# IOR8.net
KiCad netlist of a schematic drawn in EAGLE
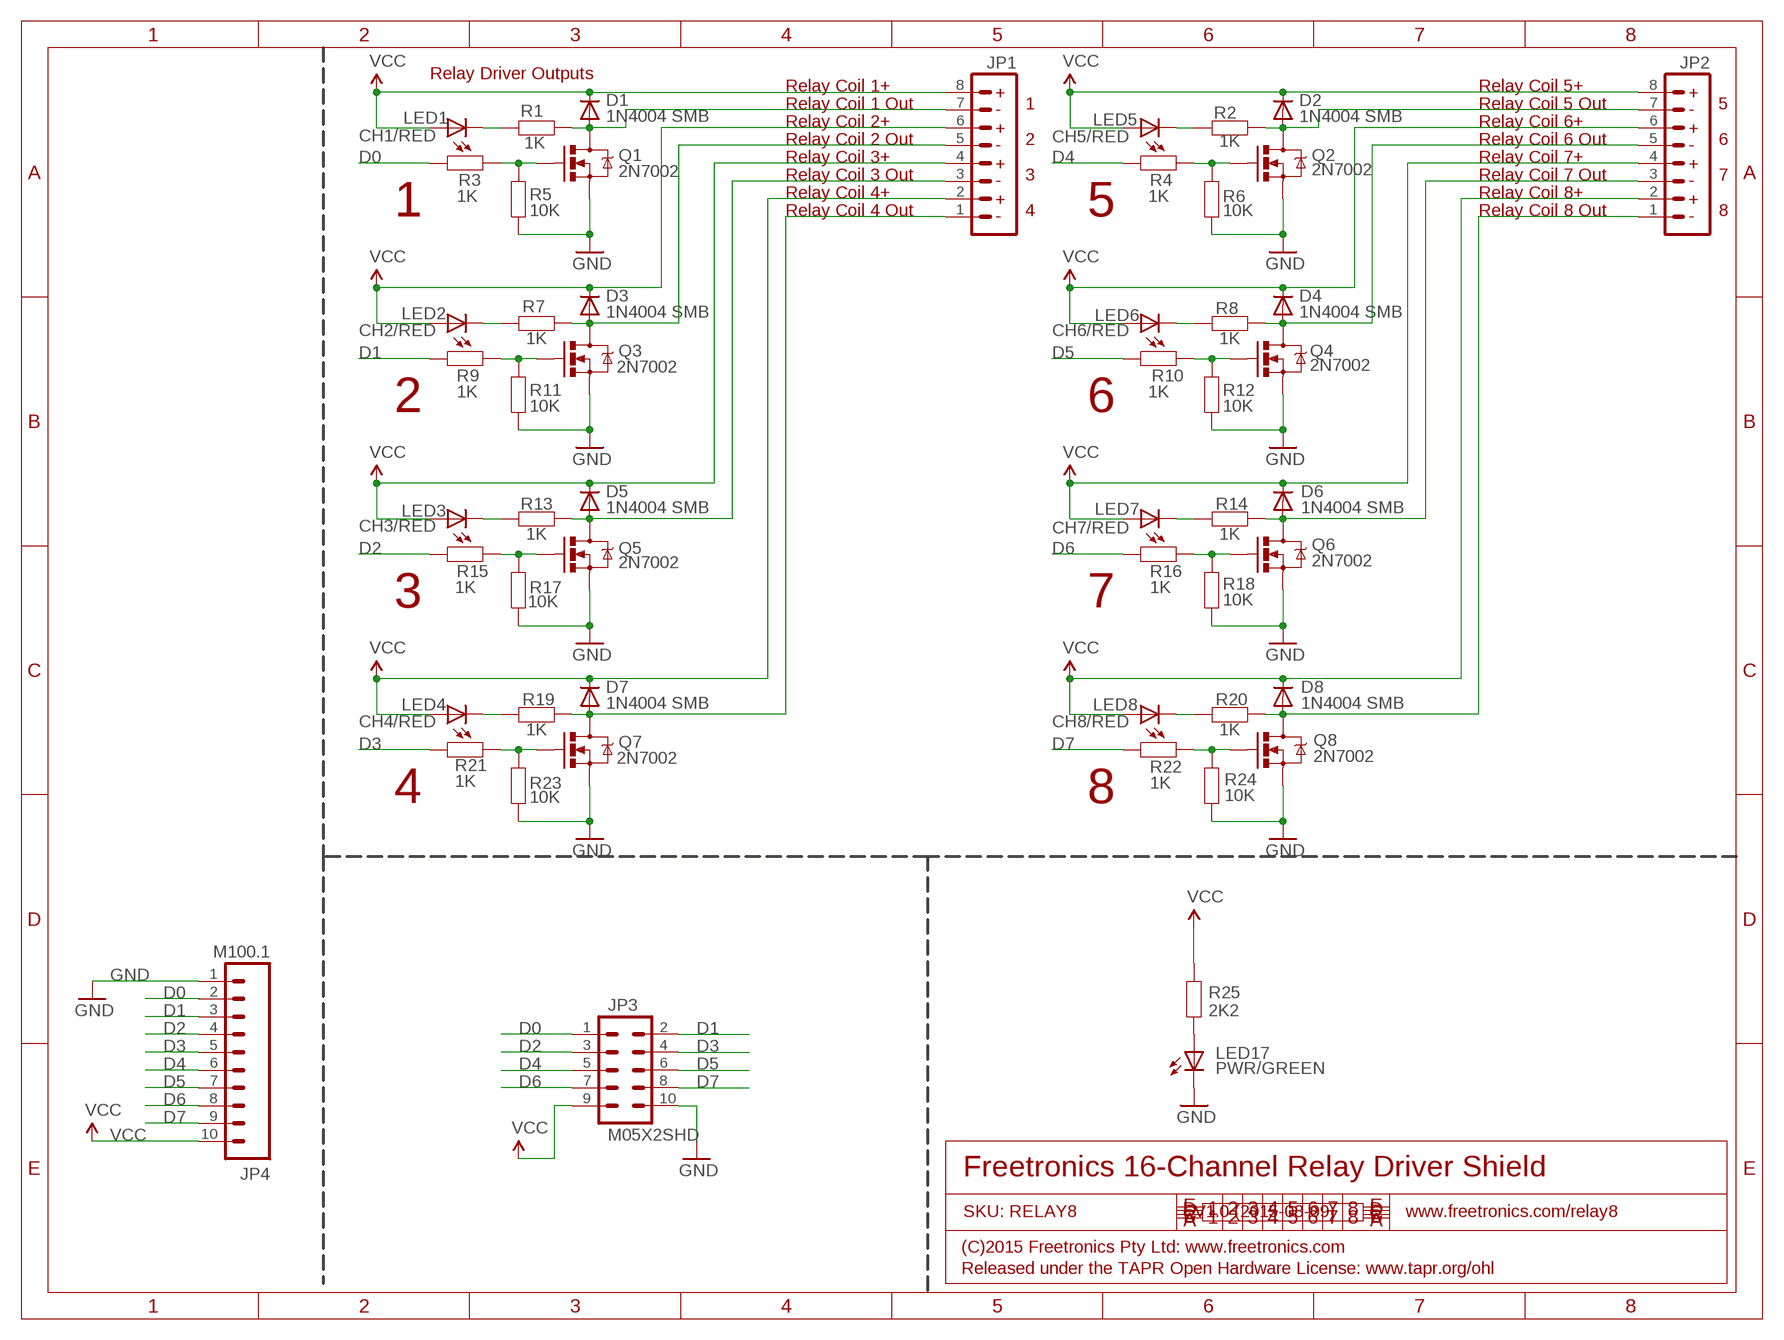
[diagram p0: schematic, sheet 1]

(export (version "E")
  (design (tool "Eeschema 10.0.6"))
  (components
    (comp (ref "D1")
      (value "1N4004 SMB")
      (footprint "eagle-import:SMB-DIODE")
      (libsource (lib "eagle-import") (part "DIODESMB"))
    )
    (comp (ref "D2")
      (value "1N4004 SMB")
      (footprint "eagle-import:SMB-DIODE")
      (libsource (lib "eagle-import") (part "DIODESMB"))
    )
    (comp (ref "D3")
      (value "1N4004 SMB")
      (footprint "eagle-import:SMB-DIODE")
      (libsource (lib "eagle-import") (part "DIODESMB"))
    )
    (comp (ref "D4")
      (value "1N4004 SMB")
      (footprint "eagle-import:SMB-DIODE")
      (libsource (lib "eagle-import") (part "DIODESMB"))
    )
    (comp (ref "D5")
      (value "1N4004 SMB")
      (footprint "eagle-import:SMB-DIODE")
      (libsource (lib "eagle-import") (part "DIODESMB"))
    )
    (comp (ref "D6")
      (value "1N4004 SMB")
      (footprint "eagle-import:SMB-DIODE")
      (libsource (lib "eagle-import") (part "DIODESMB"))
    )
    (comp (ref "D7")
      (value "1N4004 SMB")
      (footprint "eagle-import:SMB-DIODE")
      (libsource (lib "eagle-import") (part "DIODESMB"))
    )
    (comp (ref "D8")
      (value "1N4004 SMB")
      (footprint "eagle-import:SMB-DIODE")
      (libsource (lib "eagle-import") (part "DIODESMB"))
    )
    (comp (ref "JP1")
      (value "M08")
      (footprint "eagle-import:TERMINALBLOCK_3.5MM_8")
      (libsource (lib "eagle-import") (part "M08"))
    )
    (comp (ref "JP2")
      (value "M08")
      (footprint "eagle-import:TERMINALBLOCK_3.5MM_8")
      (libsource (lib "eagle-import") (part "M08"))
    )
    (comp (ref "JP3")
      (value "M05X2SHD")
      (footprint "eagle-import:2X5-SHROUDED")
      (libsource (lib "eagle-import") (part "M05X2SHD"))
    )
    (comp (ref "JP4")
      (value "M100.1")
      (footprint "eagle-import:1X10")
      (libsource (lib "eagle-import") (part "M100.1"))
    )
    (comp (ref "LED1")
      (value "CH1/RED")
      (footprint "eagle-import:LED-0603")
      (libsource (lib "eagle-import") (part "LED0603"))
    )
    (comp (ref "LED2")
      (value "CH2/RED")
      (footprint "eagle-import:LED-0603")
      (libsource (lib "eagle-import") (part "LED0603"))
    )
    (comp (ref "LED3")
      (value "CH3/RED")
      (footprint "eagle-import:LED-0603")
      (libsource (lib "eagle-import") (part "LED0603"))
    )
    (comp (ref "LED4")
      (value "CH4/RED")
      (footprint "eagle-import:LED-0603")
      (libsource (lib "eagle-import") (part "LED0603"))
    )
    (comp (ref "LED5")
      (value "CH5/RED")
      (footprint "eagle-import:LED-0603")
      (libsource (lib "eagle-import") (part "LED0603"))
    )
    (comp (ref "LED6")
      (value "CH6/RED")
      (footprint "eagle-import:LED-0603")
      (libsource (lib "eagle-import") (part "LED0603"))
    )
    (comp (ref "LED7")
      (value "CH7/RED")
      (footprint "eagle-import:LED-0603")
      (libsource (lib "eagle-import") (part "LED0603"))
    )
    (comp (ref "LED8")
      (value "CH8/RED")
      (footprint "eagle-import:LED-0603")
      (libsource (lib "eagle-import") (part "LED0603"))
    )
    (comp (ref "LED17")
      (value "PWR/GREEN")
      (footprint "eagle-import:LED-0603")
      (libsource (lib "eagle-import") (part "LED0603"))
    )
    (comp (ref "Q1")
      (value "2N7002")
      (footprint "eagle-import:SOT23-3")
      (libsource (lib "eagle-import") (part "MOSFET-NCHANNELSMD"))
    )
    (comp (ref "Q2")
      (value "2N7002")
      (footprint "eagle-import:SOT23-3")
      (libsource (lib "eagle-import") (part "MOSFET-NCHANNELSMD"))
    )
    (comp (ref "Q3")
      (value "2N7002")
      (footprint "eagle-import:SOT23-3")
      (libsource (lib "eagle-import") (part "MOSFET-NCHANNELSMD"))
    )
    (comp (ref "Q4")
      (value "2N7002")
      (footprint "eagle-import:SOT23-3")
      (libsource (lib "eagle-import") (part "MOSFET-NCHANNELSMD"))
    )
    (comp (ref "Q5")
      (value "2N7002")
      (footprint "eagle-import:SOT23-3")
      (libsource (lib "eagle-import") (part "MOSFET-NCHANNELSMD"))
    )
    (comp (ref "Q6")
      (value "2N7002")
      (footprint "eagle-import:SOT23-3")
      (libsource (lib "eagle-import") (part "MOSFET-NCHANNELSMD"))
    )
    (comp (ref "Q7")
      (value "2N7002")
      (footprint "eagle-import:SOT23-3")
      (libsource (lib "eagle-import") (part "MOSFET-NCHANNELSMD"))
    )
    (comp (ref "Q8")
      (value "2N7002")
      (footprint "eagle-import:SOT23-3")
      (libsource (lib "eagle-import") (part "MOSFET-NCHANNELSMD"))
    )
    (comp (ref "R1")
      (value "1K")
      (footprint "eagle-import:0603")
      (libsource (lib "eagle-import") (part "RESISTOR0603"))
    )
    (comp (ref "R2")
      (value "1K")
      (footprint "eagle-import:0603")
      (libsource (lib "eagle-import") (part "RESISTOR0603"))
    )
    (comp (ref "R3")
      (value "1K")
      (footprint "eagle-import:0603")
      (libsource (lib "eagle-import") (part "RESISTOR0603"))
    )
    (comp (ref "R4")
      (value "1K")
      (footprint "eagle-import:0603")
      (libsource (lib "eagle-import") (part "RESISTOR0603"))
    )
    (comp (ref "R5")
      (value "10K")
      (footprint "eagle-import:0603")
      (libsource (lib "eagle-import") (part "RESISTOR0603"))
    )
    (comp (ref "R6")
      (value "10K")
      (footprint "eagle-import:0603")
      (libsource (lib "eagle-import") (part "RESISTOR0603"))
    )
    (comp (ref "R7")
      (value "1K")
      (footprint "eagle-import:0603")
      (libsource (lib "eagle-import") (part "RESISTOR0603"))
    )
    (comp (ref "R8")
      (value "1K")
      (footprint "eagle-import:0603")
      (libsource (lib "eagle-import") (part "RESISTOR0603"))
    )
    (comp (ref "R9")
      (value "1K")
      (footprint "eagle-import:0603")
      (libsource (lib "eagle-import") (part "RESISTOR0603"))
    )
    (comp (ref "R10")
      (value "1K")
      (footprint "eagle-import:0603")
      (libsource (lib "eagle-import") (part "RESISTOR0603"))
    )
    (comp (ref "R11")
      (value "10K")
      (footprint "eagle-import:0603")
      (libsource (lib "eagle-import") (part "RESISTOR0603"))
    )
    (comp (ref "R12")
      (value "10K")
      (footprint "eagle-import:0603")
      (libsource (lib "eagle-import") (part "RESISTOR0603"))
    )
    (comp (ref "R13")
      (value "1K")
      (footprint "eagle-import:0603")
      (libsource (lib "eagle-import") (part "RESISTOR0603"))
    )
    (comp (ref "R14")
      (value "1K")
      (footprint "eagle-import:0603")
      (libsource (lib "eagle-import") (part "RESISTOR0603"))
    )
    (comp (ref "R15")
      (value "1K")
      (footprint "eagle-import:0603")
      (libsource (lib "eagle-import") (part "RESISTOR0603"))
    )
    (comp (ref "R16")
      (value "1K")
      (footprint "eagle-import:0603")
      (libsource (lib "eagle-import") (part "RESISTOR0603"))
    )
    (comp (ref "R17")
      (value "10K")
      (footprint "eagle-import:0603")
      (libsource (lib "eagle-import") (part "RESISTOR0603"))
    )
    (comp (ref "R18")
      (value "10K")
      (footprint "eagle-import:0603")
      (libsource (lib "eagle-import") (part "RESISTOR0603"))
    )
    (comp (ref "R19")
      (value "1K")
      (footprint "eagle-import:0603")
      (libsource (lib "eagle-import") (part "RESISTOR0603"))
    )
    (comp (ref "R20")
      (value "1K")
      (footprint "eagle-import:0603")
      (libsource (lib "eagle-import") (part "RESISTOR0603"))
    )
    (comp (ref "R21")
      (value "1K")
      (footprint "eagle-import:0603")
      (libsource (lib "eagle-import") (part "RESISTOR0603"))
    )
    (comp (ref "R22")
      (value "1K")
      (footprint "eagle-import:0603")
      (libsource (lib "eagle-import") (part "RESISTOR0603"))
    )
    (comp (ref "R23")
      (value "10K")
      (footprint "eagle-import:0603")
      (libsource (lib "eagle-import") (part "RESISTOR0603"))
    )
    (comp (ref "R24")
      (value "10K")
      (footprint "eagle-import:0603")
      (libsource (lib "eagle-import") (part "RESISTOR0603"))
    )
    (comp (ref "R25")
      (value "2K2")
      (footprint "eagle-import:0603")
      (libsource (lib "eagle-import") (part "RESISTOR0603"))
    )
  )
  (nets
    (net (code "1") (name "/D0") (class "Default")
      (node (ref "JP3") (pin "1") (pinfunction "1_1") (pintype "passive"))
      (node (ref "JP4") (pin "2") (pinfunction "2_2") (pintype "passive"))
      (node (ref "R3") (pin "2") (pinfunction "2_2") (pintype "passive"))
    )
    (net (code "2") (name "/D1") (class "Default")
      (node (ref "JP3") (pin "2") (pinfunction "2_2") (pintype "passive"))
      (node (ref "JP4") (pin "3") (pinfunction "3_3") (pintype "passive"))
      (node (ref "R9") (pin "2") (pinfunction "2_2") (pintype "passive"))
    )
    (net (code "3") (name "/D2") (class "Default")
      (node (ref "JP3") (pin "3") (pinfunction "3_3") (pintype "passive"))
      (node (ref "JP4") (pin "4") (pinfunction "4_4") (pintype "passive"))
      (node (ref "R15") (pin "2") (pinfunction "2_2") (pintype "passive"))
    )
    (net (code "4") (name "/D3") (class "Default")
      (node (ref "JP3") (pin "4") (pinfunction "4_4") (pintype "passive"))
      (node (ref "JP4") (pin "5") (pinfunction "5_5") (pintype "passive"))
      (node (ref "R21") (pin "2") (pinfunction "2_2") (pintype "passive"))
    )
    (net (code "5") (name "/D4") (class "Default")
      (node (ref "JP3") (pin "5") (pinfunction "5_5") (pintype "passive"))
      (node (ref "JP4") (pin "6") (pinfunction "6_6") (pintype "passive"))
      (node (ref "R4") (pin "2") (pinfunction "2_2") (pintype "passive"))
    )
    (net (code "6") (name "/D5") (class "Default")
      (node (ref "JP3") (pin "6") (pinfunction "6_6") (pintype "passive"))
      (node (ref "JP4") (pin "7") (pinfunction "7_7") (pintype "passive"))
      (node (ref "R10") (pin "2") (pinfunction "2_2") (pintype "passive"))
    )
    (net (code "7") (name "/D6") (class "Default")
      (node (ref "JP3") (pin "7") (pinfunction "7_7") (pintype "passive"))
      (node (ref "JP4") (pin "8") (pinfunction "8_8") (pintype "passive"))
      (node (ref "R16") (pin "2") (pinfunction "2_2") (pintype "passive"))
    )
    (net (code "8") (name "/D7") (class "Default")
      (node (ref "JP3") (pin "8") (pinfunction "8_8") (pintype "passive"))
      (node (ref "JP4") (pin "9") (pinfunction "9_9") (pintype "passive"))
      (node (ref "R22") (pin "2") (pinfunction "2_2") (pintype "passive"))
    )
    (net (code "9") (name "GND") (class "Default")
      (node (ref "JP3") (pin "10") (pinfunction "10_10") (pintype "passive"))
      (node (ref "JP4") (pin "1") (pinfunction "1_1") (pintype "passive"))
      (node (ref "LED17") (pin "C") (pinfunction "C_C") (pintype "passive"))
      (node (ref "Q1") (pin "2") (pinfunction "S_2") (pintype "passive"))
      (node (ref "Q2") (pin "2") (pinfunction "S_2") (pintype "passive"))
      (node (ref "Q3") (pin "2") (pinfunction "S_2") (pintype "passive"))
      (node (ref "Q4") (pin "2") (pinfunction "S_2") (pintype "passive"))
      (node (ref "Q5") (pin "2") (pinfunction "S_2") (pintype "passive"))
      (node (ref "Q6") (pin "2") (pinfunction "S_2") (pintype "passive"))
      (node (ref "Q7") (pin "2") (pinfunction "S_2") (pintype "passive"))
      (node (ref "Q8") (pin "2") (pinfunction "S_2") (pintype "passive"))
      (node (ref "R11") (pin "1") (pinfunction "1_1") (pintype "passive"))
      (node (ref "R12") (pin "1") (pinfunction "1_1") (pintype "passive"))
      (node (ref "R17") (pin "1") (pinfunction "1_1") (pintype "passive"))
      (node (ref "R18") (pin "1") (pinfunction "1_1") (pintype "passive"))
      (node (ref "R23") (pin "1") (pinfunction "1_1") (pintype "passive"))
      (node (ref "R24") (pin "1") (pinfunction "1_1") (pintype "passive"))
      (node (ref "R5") (pin "1") (pinfunction "1_1") (pintype "passive"))
      (node (ref "R6") (pin "1") (pinfunction "1_1") (pintype "passive"))
    )
    (net (code "10") (name "Net-(LED1-PadC)") (class "Default")
      (node (ref "LED1") (pin "C") (pinfunction "C_C") (pintype "passive"))
      (node (ref "R1") (pin "1") (pinfunction "1_1") (pintype "passive"))
    )
    (net (code "11") (name "Net-(LED2-PadC)") (class "Default")
      (node (ref "LED2") (pin "C") (pinfunction "C_C") (pintype "passive"))
      (node (ref "R7") (pin "1") (pinfunction "1_1") (pintype "passive"))
    )
    (net (code "12") (name "Net-(LED3-PadC)") (class "Default")
      (node (ref "LED3") (pin "C") (pinfunction "C_C") (pintype "passive"))
      (node (ref "R13") (pin "1") (pinfunction "1_1") (pintype "passive"))
    )
    (net (code "13") (name "Net-(LED4-PadC)") (class "Default")
      (node (ref "LED4") (pin "C") (pinfunction "C_C") (pintype "passive"))
      (node (ref "R19") (pin "1") (pinfunction "1_1") (pintype "passive"))
    )
    (net (code "14") (name "Net-(LED5-PadC)") (class "Default")
      (node (ref "LED5") (pin "C") (pinfunction "C_C") (pintype "passive"))
      (node (ref "R2") (pin "1") (pinfunction "1_1") (pintype "passive"))
    )
    (net (code "15") (name "Net-(LED6-PadC)") (class "Default")
      (node (ref "LED6") (pin "C") (pinfunction "C_C") (pintype "passive"))
      (node (ref "R8") (pin "1") (pinfunction "1_1") (pintype "passive"))
    )
    (net (code "16") (name "Net-(LED7-PadC)") (class "Default")
      (node (ref "LED7") (pin "C") (pinfunction "C_C") (pintype "passive"))
      (node (ref "R14") (pin "1") (pinfunction "1_1") (pintype "passive"))
    )
    (net (code "17") (name "Net-(LED8-PadC)") (class "Default")
      (node (ref "LED8") (pin "C") (pinfunction "C_C") (pintype "passive"))
      (node (ref "R20") (pin "1") (pinfunction "1_1") (pintype "passive"))
    )
    (net (code "18") (name "Net-(LED17-PadA)") (class "Default")
      (node (ref "LED17") (pin "A") (pinfunction "A_A") (pintype "passive"))
      (node (ref "R25") (pin "1") (pinfunction "1_1") (pintype "passive"))
    )
    (net (code "19") (name "Net-(Q1-D)") (class "Default")
      (node (ref "D1") (pin "A") (pinfunction "A_A") (pintype "passive"))
      (node (ref "JP1") (pin "7") (pinfunction "7_7") (pintype "passive"))
      (node (ref "Q1") (pin "3") (pinfunction "D_3") (pintype "passive"))
      (node (ref "R1") (pin "2") (pinfunction "2_2") (pintype "passive"))
    )
    (net (code "20") (name "Net-(Q1-G)") (class "Default")
      (node (ref "Q1") (pin "1") (pinfunction "G_1") (pintype "passive"))
      (node (ref "R3") (pin "1") (pinfunction "1_1") (pintype "passive"))
      (node (ref "R5") (pin "2") (pinfunction "2_2") (pintype "passive"))
    )
    (net (code "21") (name "Net-(Q2-D)") (class "Default")
      (node (ref "D2") (pin "A") (pinfunction "A_A") (pintype "passive"))
      (node (ref "JP2") (pin "7") (pinfunction "7_7") (pintype "passive"))
      (node (ref "Q2") (pin "3") (pinfunction "D_3") (pintype "passive"))
      (node (ref "R2") (pin "2") (pinfunction "2_2") (pintype "passive"))
    )
    (net (code "22") (name "Net-(Q2-G)") (class "Default")
      (node (ref "Q2") (pin "1") (pinfunction "G_1") (pintype "passive"))
      (node (ref "R4") (pin "1") (pinfunction "1_1") (pintype "passive"))
      (node (ref "R6") (pin "2") (pinfunction "2_2") (pintype "passive"))
    )
    (net (code "23") (name "Net-(Q3-D)") (class "Default")
      (node (ref "D3") (pin "A") (pinfunction "A_A") (pintype "passive"))
      (node (ref "JP1") (pin "5") (pinfunction "5_5") (pintype "passive"))
      (node (ref "Q3") (pin "3") (pinfunction "D_3") (pintype "passive"))
      (node (ref "R7") (pin "2") (pinfunction "2_2") (pintype "passive"))
    )
    (net (code "24") (name "Net-(Q3-G)") (class "Default")
      (node (ref "Q3") (pin "1") (pinfunction "G_1") (pintype "passive"))
      (node (ref "R11") (pin "2") (pinfunction "2_2") (pintype "passive"))
      (node (ref "R9") (pin "1") (pinfunction "1_1") (pintype "passive"))
    )
    (net (code "25") (name "Net-(Q4-D)") (class "Default")
      (node (ref "D4") (pin "A") (pinfunction "A_A") (pintype "passive"))
      (node (ref "JP2") (pin "5") (pinfunction "5_5") (pintype "passive"))
      (node (ref "Q4") (pin "3") (pinfunction "D_3") (pintype "passive"))
      (node (ref "R8") (pin "2") (pinfunction "2_2") (pintype "passive"))
    )
    (net (code "26") (name "Net-(Q4-G)") (class "Default")
      (node (ref "Q4") (pin "1") (pinfunction "G_1") (pintype "passive"))
      (node (ref "R10") (pin "1") (pinfunction "1_1") (pintype "passive"))
      (node (ref "R12") (pin "2") (pinfunction "2_2") (pintype "passive"))
    )
    (net (code "27") (name "Net-(Q5-D)") (class "Default")
      (node (ref "D5") (pin "A") (pinfunction "A_A") (pintype "passive"))
      (node (ref "JP1") (pin "3") (pinfunction "3_3") (pintype "passive"))
      (node (ref "Q5") (pin "3") (pinfunction "D_3") (pintype "passive"))
      (node (ref "R13") (pin "2") (pinfunction "2_2") (pintype "passive"))
    )
    (net (code "28") (name "Net-(Q5-G)") (class "Default")
      (node (ref "Q5") (pin "1") (pinfunction "G_1") (pintype "passive"))
      (node (ref "R15") (pin "1") (pinfunction "1_1") (pintype "passive"))
      (node (ref "R17") (pin "2") (pinfunction "2_2") (pintype "passive"))
    )
    (net (code "29") (name "Net-(Q6-D)") (class "Default")
      (node (ref "D6") (pin "A") (pinfunction "A_A") (pintype "passive"))
      (node (ref "JP2") (pin "3") (pinfunction "3_3") (pintype "passive"))
      (node (ref "Q6") (pin "3") (pinfunction "D_3") (pintype "passive"))
      (node (ref "R14") (pin "2") (pinfunction "2_2") (pintype "passive"))
    )
    (net (code "30") (name "Net-(Q6-G)") (class "Default")
      (node (ref "Q6") (pin "1") (pinfunction "G_1") (pintype "passive"))
      (node (ref "R16") (pin "1") (pinfunction "1_1") (pintype "passive"))
      (node (ref "R18") (pin "2") (pinfunction "2_2") (pintype "passive"))
    )
    (net (code "31") (name "Net-(Q7-D)") (class "Default")
      (node (ref "D7") (pin "A") (pinfunction "A_A") (pintype "passive"))
      (node (ref "JP1") (pin "1") (pinfunction "1_1") (pintype "passive"))
      (node (ref "Q7") (pin "3") (pinfunction "D_3") (pintype "passive"))
      (node (ref "R19") (pin "2") (pinfunction "2_2") (pintype "passive"))
    )
    (net (code "32") (name "Net-(Q7-G)") (class "Default")
      (node (ref "Q7") (pin "1") (pinfunction "G_1") (pintype "passive"))
      (node (ref "R21") (pin "1") (pinfunction "1_1") (pintype "passive"))
      (node (ref "R23") (pin "2") (pinfunction "2_2") (pintype "passive"))
    )
    (net (code "33") (name "Net-(Q8-D)") (class "Default")
      (node (ref "D8") (pin "A") (pinfunction "A_A") (pintype "passive"))
      (node (ref "JP2") (pin "1") (pinfunction "1_1") (pintype "passive"))
      (node (ref "Q8") (pin "3") (pinfunction "D_3") (pintype "passive"))
      (node (ref "R20") (pin "2") (pinfunction "2_2") (pintype "passive"))
    )
    (net (code "34") (name "Net-(Q8-G)") (class "Default")
      (node (ref "Q8") (pin "1") (pinfunction "G_1") (pintype "passive"))
      (node (ref "R22") (pin "1") (pinfunction "1_1") (pintype "passive"))
      (node (ref "R24") (pin "2") (pinfunction "2_2") (pintype "passive"))
    )
    (net (code "35") (name "VCC") (class "Default")
      (node (ref "D1") (pin "C") (pinfunction "C_C") (pintype "passive"))
      (node (ref "D2") (pin "C") (pinfunction "C_C") (pintype "passive"))
      (node (ref "D3") (pin "C") (pinfunction "C_C") (pintype "passive"))
      (node (ref "D4") (pin "C") (pinfunction "C_C") (pintype "passive"))
      (node (ref "D5") (pin "C") (pinfunction "C_C") (pintype "passive"))
      (node (ref "D6") (pin "C") (pinfunction "C_C") (pintype "passive"))
      (node (ref "D7") (pin "C") (pinfunction "C_C") (pintype "passive"))
      (node (ref "D8") (pin "C") (pinfunction "C_C") (pintype "passive"))
      (node (ref "JP1") (pin "2") (pinfunction "2_2") (pintype "passive"))
      (node (ref "JP1") (pin "4") (pinfunction "4_4") (pintype "passive"))
      (node (ref "JP1") (pin "6") (pinfunction "6_6") (pintype "passive"))
      (node (ref "JP1") (pin "8") (pinfunction "8_8") (pintype "passive"))
      (node (ref "JP2") (pin "2") (pinfunction "2_2") (pintype "passive"))
      (node (ref "JP2") (pin "4") (pinfunction "4_4") (pintype "passive"))
      (node (ref "JP2") (pin "6") (pinfunction "6_6") (pintype "passive"))
      (node (ref "JP2") (pin "8") (pinfunction "8_8") (pintype "passive"))
      (node (ref "JP3") (pin "9") (pinfunction "9_9") (pintype "passive"))
      (node (ref "JP4") (pin "10") (pinfunction "10_10") (pintype "passive"))
      (node (ref "LED1") (pin "A") (pinfunction "A_A") (pintype "passive"))
      (node (ref "LED2") (pin "A") (pinfunction "A_A") (pintype "passive"))
      (node (ref "LED3") (pin "A") (pinfunction "A_A") (pintype "passive"))
      (node (ref "LED4") (pin "A") (pinfunction "A_A") (pintype "passive"))
      (node (ref "LED5") (pin "A") (pinfunction "A_A") (pintype "passive"))
      (node (ref "LED6") (pin "A") (pinfunction "A_A") (pintype "passive"))
      (node (ref "LED7") (pin "A") (pinfunction "A_A") (pintype "passive"))
      (node (ref "LED8") (pin "A") (pinfunction "A_A") (pintype "passive"))
      (node (ref "R25") (pin "2") (pinfunction "2_2") (pintype "passive"))
    )
  )
)
